# nand.net
KiCad netlist of a schematic drawn in EAGLE
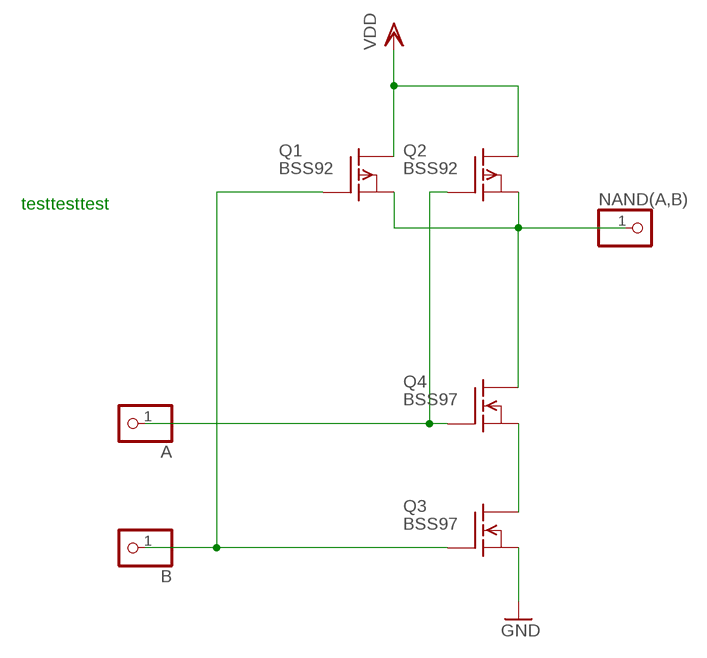
[diagram p0: schematic, sheet 1]

(export (version "E")
  (design (tool "Eeschema 10.0.6"))
  (components
    (comp (ref "A")
      (value "PINHD-1X1")
      (footprint "eagle-import:1X01")
      (libsource (lib "eagle-import") (part "PINHD-1X1"))
    )
    (comp (ref "B")
      (value "PINHD-1X1")
      (footprint "eagle-import:1X01")
      (libsource (lib "eagle-import") (part "PINHD-1X1"))
    )
    (comp (ref "NAND(A,B)")
      (value "PINHD-1X1")
      (footprint "eagle-import:1X01")
      (libsource (lib "eagle-import") (part "PINHD-1X1"))
    )
    (comp (ref "Q1")
      (value "BSS92")
      (footprint "eagle-import:TO92")
      (libsource (lib "eagle-import") (part "BSS92"))
    )
    (comp (ref "Q2")
      (value "BSS92")
      (footprint "eagle-import:TO92")
      (libsource (lib "eagle-import") (part "BSS92"))
    )
    (comp (ref "Q3")
      (value "BSS97")
      (footprint "eagle-import:TO202")
      (libsource (lib "eagle-import") (part "BSS97"))
    )
    (comp (ref "Q4")
      (value "BSS97")
      (footprint "eagle-import:TO202")
      (libsource (lib "eagle-import") (part "BSS97"))
    )
  )
  (nets
    (net (code "1") (name "GND") (class "Default")
      (node (ref "Q3") (pin "1") (pinfunction "S_1") (pintype "passive"))
    )
    (net (code "2") (name "Net-(Q1-G)") (class "Default")
      (node (ref "B") (pin "1") (pinfunction "1_1") (pintype "passive"))
      (node (ref "Q1") (pin "1") (pinfunction "G_1") (pintype "passive"))
      (node (ref "Q3") (pin "3") (pinfunction "G_3") (pintype "passive"))
    )
    (net (code "3") (name "Net-(Q1-S)") (class "Default")
      (node (ref "NAND(A,B)") (pin "1") (pinfunction "1_1") (pintype "passive"))
      (node (ref "Q1") (pin "3") (pinfunction "S_3") (pintype "passive"))
      (node (ref "Q2") (pin "3") (pinfunction "S_3") (pintype "passive"))
      (node (ref "Q4") (pin "2") (pinfunction "D_2") (pintype "passive"))
    )
    (net (code "4") (name "Net-(Q2-G)") (class "Default")
      (node (ref "A") (pin "1") (pinfunction "1_1") (pintype "passive"))
      (node (ref "Q2") (pin "1") (pinfunction "G_1") (pintype "passive"))
      (node (ref "Q4") (pin "3") (pinfunction "G_3") (pintype "passive"))
    )
    (net (code "5") (name "Net-(Q3-D)") (class "Default")
      (node (ref "Q3") (pin "2") (pinfunction "D_2") (pintype "passive"))
      (node (ref "Q4") (pin "1") (pinfunction "S_1") (pintype "passive"))
    )
    (net (code "6") (name "VDD") (class "Default")
      (node (ref "Q1") (pin "2") (pinfunction "D_2") (pintype "passive"))
      (node (ref "Q2") (pin "2") (pinfunction "D_2") (pintype "passive"))
    )
  )
)
